# MICRO.net
KiCad netlist of a schematic drawn in Altium Designer
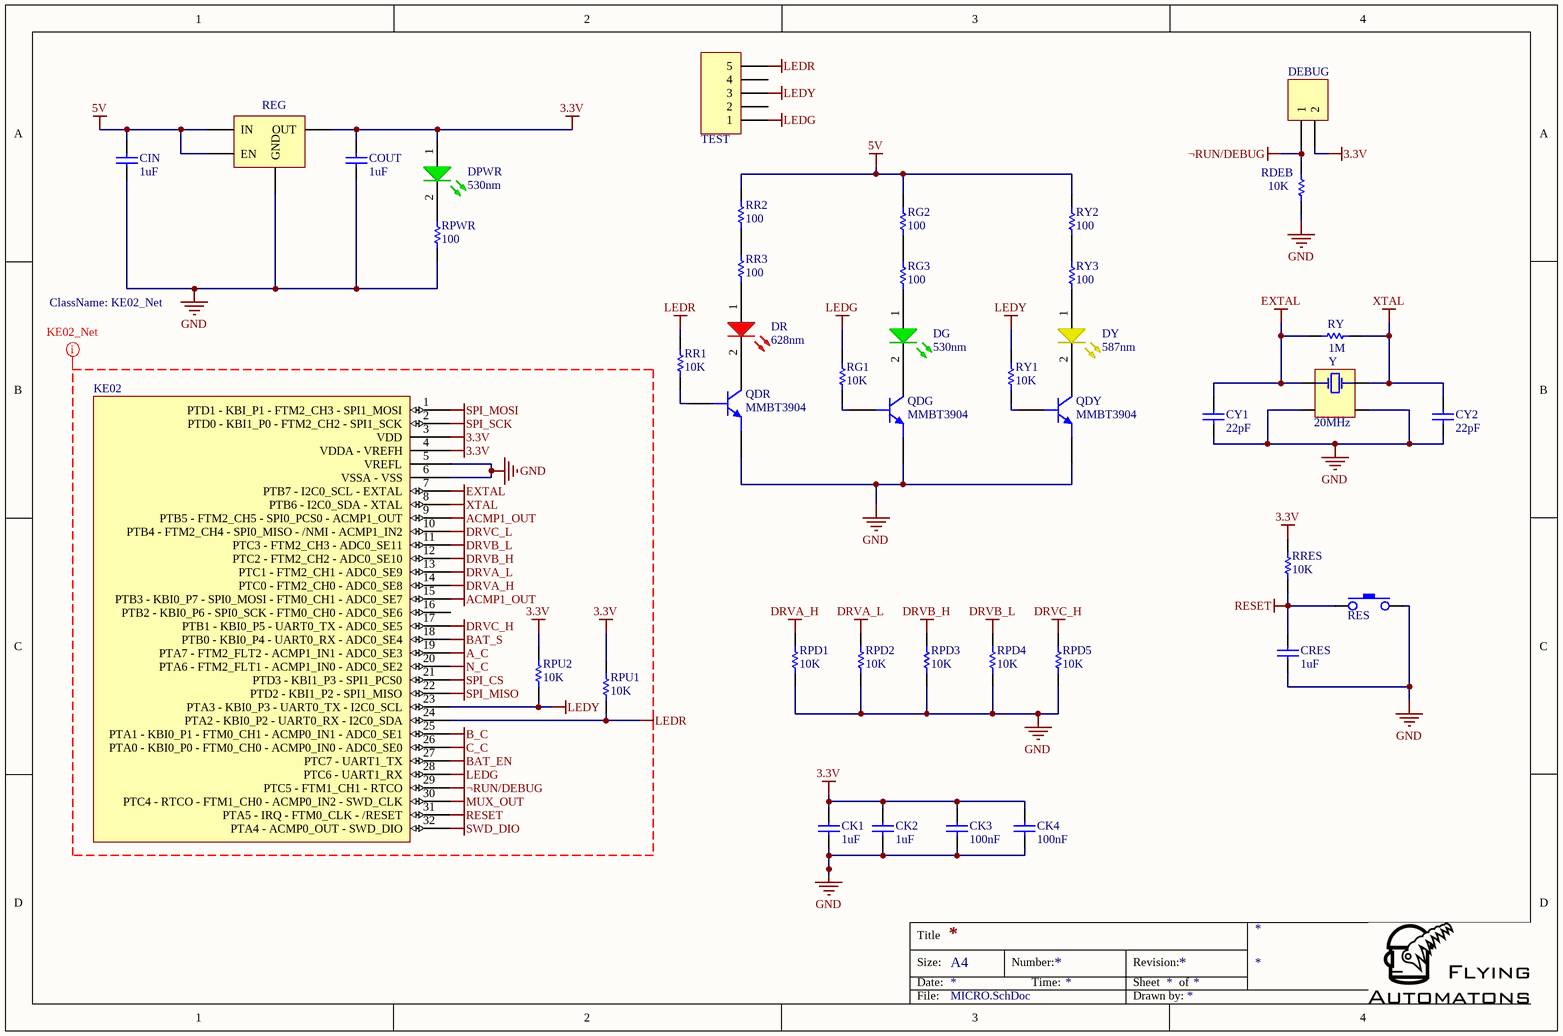
[diagram p0: MICRO.SchDoc]

(export (version "E")
  (design (tool "Eeschema 10.0.6"))
  (components
    (comp (ref "CIN")
      (value "1uF")
      (footprint "CAPC1608L")
      (description "CAP CER 1UF 25V 10% X5R 0603")
      (fields (field (name "MANUFACTURER PART NUMBER") "TMK107BJ105KA-T"))
      (libsource (lib "Passive#csv") (part "CAP_1u_0603_25V_X5R_10%"))
    )
    (comp (ref "CK1")
      (value "1uF")
      (footprint "CAPC1608L")
      (description "CAP CER 1UF 25V 10% X5R 0603")
      (fields (field (name "MANUFACTURER PART NUMBER") "TMK107BJ105KA-T"))
      (libsource (lib "Passive#csv") (part "CAP_1u_0603_25V_X5R_10%"))
    )
    (comp (ref "CK2")
      (value "1uF")
      (footprint "CAPC1608L")
      (description "CAP CER 1UF 25V 10% X5R 0603")
      (fields (field (name "MANUFACTURER PART NUMBER") "TMK107BJ105KA-T"))
      (libsource (lib "Passive#csv") (part "CAP_1u_0603_25V_X5R_10%"))
    )
    (comp (ref "CK3")
      (value "100nF")
      (footprint "CAPC1608L")
      (description "CAP CER 0.1UF 50V Y5V 0603")
      (fields (field (name "MANUFACTURER PART NUMBER") "CC0603ZRY5V9BB104"))
      (libsource (lib "Passive#csv") (part "CAP_100n_0603_50V_Y5V"))
    )
    (comp (ref "CK4")
      (value "100nF")
      (footprint "CAPC1608L")
      (description "CAP CER 0.1UF 50V Y5V 0603")
      (fields (field (name "MANUFACTURER PART NUMBER") "CC0603ZRY5V9BB104"))
      (libsource (lib "Passive#csv") (part "CAP_100n_0603_50V_Y5V"))
    )
    (comp (ref "COUT")
      (value "1uF")
      (footprint "CAPC1608L")
      (description "CAP CER 1UF 25V 10% X5R 0603")
      (fields (field (name "MANUFACTURER PART NUMBER") "TMK107BJ105KA-T"))
      (libsource (lib "Passive#csv") (part "CAP_1u_0603_25V_X5R_10%"))
    )
    (comp (ref "CRES")
      (value "1uF")
      (footprint "CAPC1608L")
      (description "CAP CER 1UF 25V 10% X5R 0603")
      (fields (field (name "MANUFACTURER PART NUMBER") "TMK107BJ105KA-T"))
      (libsource (lib "Passive#csv") (part "CAP_1u_0603_25V_X5R_10%"))
    )
    (comp (ref "CY1")
      (value "22pF")
      (footprint "CAPC1608L")
      (description "CAP CER 22PF 50V 5% NP0 0603")
      (fields (field (name "MANUFACTURER PART NUMBER") "CL10C220JB8NCNC"))
      (libsource (lib "Passive#csv") (part "CAP_22p_0603_50V_NP0_5%"))
    )
    (comp (ref "CY2")
      (value "22pF")
      (footprint "CAPC1608L")
      (description "CAP CER 22PF 50V 5% NP0 0603")
      (fields (field (name "MANUFACTURER PART NUMBER") "CL10C220JB8NCNC"))
      (libsource (lib "Passive#csv") (part "CAP_22p_0603_50V_NP0_5%"))
    )
    (comp (ref "DEBUG")
      (value "Header 2")
      (footprint "Pines 1x2")
      (description "Header, 2-Pin")
      (fields (field (name "PUBLISHER") "Altium Limited"))
      (libsource (lib "ConnectorsGordo") (part "Header 2"))
    )
    (comp (ref "DG")
      (value "530nm")
      (footprint "DSO-F2/D3.4")
      (description "LED CHIPLED 570NM GREEN 0603 SMD")
      (fields
        (field (name "MANUFACTURER") "OSRAM Opto Semiconductors Inc")
        (field (name "MANUFACTURER PART NUMBER") "LG Q971-KN-1")
        (field (name "DRAWN BY") "Juan I Carrano")
      )
      (libsource (lib "Discrete#csv") (part "LED_GREEN_0603_530"))
    )
    (comp (ref "DPWR")
      (value "530nm")
      (footprint "DSO-F2/D3.4")
      (description "LED CHIPLED 570NM GREEN 0603 SMD")
      (fields
        (field (name "MANUFACTURER") "OSRAM Opto Semiconductors Inc")
        (field (name "MANUFACTURER PART NUMBER") "LG Q971-KN-1")
        (field (name "DRAWN BY") "Juan I Carrano")
      )
      (libsource (lib "Discrete#csv") (part "LED_GREEN_0603_530"))
    )
    (comp (ref "DR")
      (value "628nm")
      (footprint "DSO-F2/D3.4")
      (description "LED POINTLED 628NM SUPER RED SMD")
      (fields
        (field (name "MANUFACTURER") "OSRAM Opto Semiconductors Inc")
        (field (name "MANUFACTURER PART NUMBER") "LS Q971-KN-1")
        (field (name "DRAWN BY") "Juan I Carrano")
      )
      (libsource (lib "Discrete#csv") (part "LED_RED_0603_628"))
    )
    (comp (ref "DY")
      (value "587nm")
      (footprint "DSO-F2/D3.4")
      (description "LED CHIPLED 587NM YLW 0603 SMD")
      (fields
        (field (name "MANUFACTURER") "OSRAM Opto Semiconductors Inc")
        (field (name "MANUFACTURER PART NUMBER") "LY Q976-P1S2-36")
        (field (name "DRAWN BY") "Juan I Carrano")
      )
      (libsource (lib "Discrete#csv") (part "LED_YELLOW_0603_587"))
    )
    (comp (ref "KE02")
      (value "MKE02ZxxVLC2(R)")
      (footprint "JEDEC_MS-026BBA")
      (description "Kinetis KE02 Cortex®-M0+ MCU 32 Pin LQFP")
      (fields
        (field (name "MANUFACTURER") "Freescale")
        (field (name "MANUFACTURER PART NUMBER") "MKE02Z64VLC2(R)")
      )
      (libsource (lib "MCU#csv") (part "MKE02Z64VLC2(R)"))
    )
    (comp (ref "QDG")
      (value "MMBT3904")
      (footprint "SOT23-3L")
      (description "TRANSISTOR NPN 40V 0.2A SOT23")
      (fields (field (name "MANUFACTURER") "NXP Semiconductors") (field (name "Comment") "BJT-NPN-BEC"))
      (libsource (lib "Discrete#csv") (part "MMBT3904"))
    )
    (comp (ref "QDR")
      (value "MMBT3904")
      (footprint "SOT23-3L")
      (description "TRANSISTOR NPN 40V 0.2A SOT23")
      (fields (field (name "MANUFACTURER") "NXP Semiconductors") (field (name "Comment") "BJT-NPN-BEC"))
      (libsource (lib "Discrete#csv") (part "MMBT3904"))
    )
    (comp (ref "QDY")
      (value "MMBT3904")
      (footprint "SOT23-3L")
      (description "TRANSISTOR NPN 40V 0.2A SOT23")
      (fields (field (name "MANUFACTURER") "NXP Semiconductors") (field (name "Comment") "BJT-NPN-BEC"))
      (libsource (lib "Discrete#csv") (part "MMBT3904"))
    )
    (comp (ref "RDEB")
      (value "10K")
      (footprint "RESC1608L")
      (description "RES 10K OHM 1/10W 5% 0603")
      (fields (field (name "MANUFACTURER PART NUMBER") "RC1608J103CS"))
      (libsource (lib "Passive#csv") (part "RES_10K_0603_0W1_1%"))
    )
    (comp (ref "REG")
      (value "LP5900")
      (footprint "x-TI_S-NGF0006A")
      (description "IC REG LDO 3.3V 0.15A 6WSON")
      (fields
        (field (name "MANUFACTURER") "Texas Instruments")
        (field (name "MANUFACTURER PART NUMBER") "LP5900SD-3.3/NOPB")
      )
      (libsource (lib "Power_IC#csv") (part "x-TI_LP5900"))
    )
    (comp (ref "RES")
      (value "SWITCH_TACTILE_SPST-2T-NO")
      (footprint "X-TECO_FSMSM")
      (description "SWITCH TACTILE SPST-NO 0.05A 12V")
      (fields
        (field (name "MANUFACTURER") "TE Connectivity")
        (field (name "MANUFACTURER PART NUMBER") "FSMSM")
      )
      (libsource (lib "Switch#csv") (part "SW_TACT_3.5x6mm_SMT"))
    )
    (comp (ref "RG1")
      (value "10K")
      (footprint "RESC1608L")
      (description "RES 10K OHM 1/10W 5% 0603")
      (fields (field (name "MANUFACTURER PART NUMBER") "RC1608J103CS"))
      (libsource (lib "Passive#csv") (part "RES_10K_0603_0W1_1%"))
    )
    (comp (ref "RG2")
      (value "100")
      (footprint "RESC1608L")
      (description "RES 100 OHM 1/10W 5% 0603 SMD")
      (fields (field (name "MANUFACTURER PART NUMBER") "RC0603JR-07100RL"))
      (libsource (lib "Passive#csv") (part "RES_100_0603_0W1_1%"))
    )
    (comp (ref "RG3")
      (value "100")
      (footprint "RESC1608L")
      (description "RES 100 OHM 1/10W 5% 0603 SMD")
      (fields (field (name "MANUFACTURER PART NUMBER") "RC0603JR-07100RL"))
      (libsource (lib "Passive#csv") (part "RES_100_0603_0W1_1%"))
    )
    (comp (ref "RPD1")
      (value "10K")
      (footprint "RESC1608L")
      (description "RES 10K OHM 1/10W 5% 0603")
      (fields (field (name "MANUFACTURER PART NUMBER") "RC1608J103CS"))
      (libsource (lib "Passive#csv") (part "RES_10K_0603_0W1_1%"))
    )
    (comp (ref "RPD2")
      (value "10K")
      (footprint "RESC1608L")
      (description "RES 10K OHM 1/10W 5% 0603")
      (fields (field (name "MANUFACTURER PART NUMBER") "RC1608J103CS"))
      (libsource (lib "Passive#csv") (part "RES_10K_0603_0W1_1%"))
    )
    (comp (ref "RPD3")
      (value "10K")
      (footprint "RESC1608L")
      (description "RES 10K OHM 1/10W 5% 0603")
      (fields (field (name "MANUFACTURER PART NUMBER") "RC1608J103CS"))
      (libsource (lib "Passive#csv") (part "RES_10K_0603_0W1_1%"))
    )
    (comp (ref "RPD4")
      (value "10K")
      (footprint "RESC1608L")
      (description "RES 10K OHM 1/10W 5% 0603")
      (fields (field (name "MANUFACTURER PART NUMBER") "RC1608J103CS"))
      (libsource (lib "Passive#csv") (part "RES_10K_0603_0W1_1%"))
    )
    (comp (ref "RPD5")
      (value "10K")
      (footprint "RESC1608L")
      (description "RES 10K OHM 1/10W 5% 0603")
      (fields (field (name "MANUFACTURER PART NUMBER") "RC1608J103CS"))
      (libsource (lib "Passive#csv") (part "RES_10K_0603_0W1_1%"))
    )
    (comp (ref "RPU1")
      (value "10K")
      (footprint "RESC1608L")
      (description "RES 10K OHM 1/10W 5% 0603")
      (fields (field (name "MANUFACTURER PART NUMBER") "RC1608J103CS"))
      (libsource (lib "Passive#csv") (part "RES_10K_0603_0W1_1%"))
    )
    (comp (ref "RPU2")
      (value "10K")
      (footprint "RESC1608L")
      (description "RES 10K OHM 1/10W 5% 0603")
      (fields (field (name "MANUFACTURER PART NUMBER") "RC1608J103CS"))
      (libsource (lib "Passive#csv") (part "RES_10K_0603_0W1_1%"))
    )
    (comp (ref "RPWR")
      (value "100")
      (footprint "RESC1608L")
      (description "RES 100 OHM 1/10W 5% 0603 SMD")
      (fields (field (name "MANUFACTURER PART NUMBER") "RC0603JR-07100RL"))
      (libsource (lib "Passive#csv") (part "RES_100_0603_0W1_1%"))
    )
    (comp (ref "RR1")
      (value "10K")
      (footprint "RESC1608L")
      (description "RES 10K OHM 1/10W 5% 0603")
      (fields (field (name "MANUFACTURER PART NUMBER") "RC1608J103CS"))
      (libsource (lib "Passive#csv") (part "RES_10K_0603_0W1_1%"))
    )
    (comp (ref "RR2")
      (value "100")
      (footprint "RESC1608L")
      (description "RES 100 OHM 1/10W 5% 0603 SMD")
      (fields (field (name "MANUFACTURER PART NUMBER") "RC0603JR-07100RL"))
      (libsource (lib "Passive#csv") (part "RES_100_0603_0W1_1%"))
    )
    (comp (ref "RR3")
      (value "100")
      (footprint "RESC1608L")
      (description "RES 100 OHM 1/10W 5% 0603 SMD")
      (fields (field (name "MANUFACTURER PART NUMBER") "RC0603JR-07100RL"))
      (libsource (lib "Passive#csv") (part "RES_100_0603_0W1_1%"))
    )
    (comp (ref "RRES")
      (value "10K")
      (footprint "RESC1608L")
      (description "RES 10K OHM 1/10W 5% 0603")
      (fields (field (name "MANUFACTURER PART NUMBER") "RC1608J103CS"))
      (libsource (lib "Passive#csv") (part "RES_10K_0603_0W1_1%"))
    )
    (comp (ref "RY")
      (value "1M")
      (footprint "RESC1608L")
      (description "RES 1.00M OHM 1/10W 1% 0603 SMD")
      (fields
        (field (name "MANUFACTURER") "Yageo")
        (field (name "MANUFACTURER PART NUMBER") "RC0603FR-071ML")
      )
      (libsource (lib "Passive#csv") (part "RES_1M_0603_0W1_1%"))
    )
    (comp (ref "RY1")
      (value "10K")
      (footprint "RESC1608L")
      (description "RES 10K OHM 1/10W 5% 0603")
      (fields (field (name "MANUFACTURER PART NUMBER") "RC1608J103CS"))
      (libsource (lib "Passive#csv") (part "RES_10K_0603_0W1_1%"))
    )
    (comp (ref "RY2")
      (value "100")
      (footprint "RESC1608L")
      (description "RES 100 OHM 1/10W 5% 0603 SMD")
      (fields (field (name "MANUFACTURER PART NUMBER") "RC0603JR-07100RL"))
      (libsource (lib "Passive#csv") (part "RES_100_0603_0W1_1%"))
    )
    (comp (ref "RY3")
      (value "100")
      (footprint "RESC1608L")
      (description "RES 100 OHM 1/10W 5% 0603 SMD")
      (fields (field (name "MANUFACTURER PART NUMBER") "RC0603JR-07100RL"))
      (libsource (lib "Passive#csv") (part "RES_100_0603_0W1_1%"))
    )
    (comp (ref "TEST")
      (value "Header 5")
      (footprint "Pines 1x5")
      (description "Header, 5-Pin")
      (fields (field (name "PUBLISHER") "Altium Limited"))
      (libsource (lib "ConnectorsGordo") (part "Header 5"))
    )
    (comp (ref "Y")
      (value "20MHz")
      (footprint "X-EPSO_TSX-3225")
      (description "CRYSTAL 20MHZ 9PF SMD")
      (fields
        (field (name "MANUFACTURER") "EPSON")
        (field (name "MANUFACTURER PART NUMBER") "TSX-3225 20.0000MF20G-AC3")
        (field (name "DRAWN BY") "Juan I Carrano")
      )
      (libsource (lib "Passive#csv") (part "XTAL_20M_SMD_9p"))
    )
  )
  (nets
    (net (code "1") (name "3.3V") (class "Default")
      (node (ref "CK1") (pin "1") (pinfunction "1_1") (pintype "passive"))
      (node (ref "CK2") (pin "1") (pinfunction "1_1") (pintype "passive"))
      (node (ref "CK3") (pin "1") (pinfunction "1_1") (pintype "passive"))
      (node (ref "CK4") (pin "1") (pinfunction "1_1") (pintype "passive"))
      (node (ref "COUT") (pin "1") (pinfunction "1_1") (pintype "passive"))
      (node (ref "DEBUG") (pin "2") (pinfunction "2_2") (pintype "passive"))
      (node (ref "DPWR") (pin "1") (pinfunction "A_1") (pintype "passive"))
      (node (ref "KE02") (pin "3") (pinfunction "VDD_3") (pintype "passive"))
      (node (ref "KE02") (pin "4") (pinfunction "VDDA_-_VREFH_4") (pintype "passive"))
      (node (ref "REG") (pin "1") (pinfunction "OUT_1") (pintype "passive"))
      (node (ref "RPU1") (pin "1") (pinfunction "1_1") (pintype "passive"))
      (node (ref "RPU2") (pin "1") (pinfunction "1_1") (pintype "passive"))
      (node (ref "RRES") (pin "1") (pinfunction "1_1") (pintype "passive"))
    )
    (net (code "2") (name "5V") (class "Default")
      (node (ref "CIN") (pin "1") (pinfunction "1_1") (pintype "passive"))
      (node (ref "REG") (pin "4") (pinfunction "EN_4") (pintype "passive"))
      (node (ref "REG") (pin "6") (pinfunction "IN_6") (pintype "passive"))
      (node (ref "RG2") (pin "1") (pinfunction "1_1") (pintype "passive"))
      (node (ref "RR2") (pin "1") (pinfunction "1_1") (pintype "passive"))
      (node (ref "RY2") (pin "1") (pinfunction "1_1") (pintype "passive"))
    )
    (net (code "3") (name "ACMP1_OUT") (class "Default")
      (node (ref "KE02") (pin "15") (pinfunction "PTB3_-_KBI0_P7_-_SPI0_MOSI_-_FTM0_CH1_-_ADC0_SE7_15") (pintype "bidirectional"))
      (node (ref "KE02") (pin "9") (pinfunction "PTB5_-_FTM2_CH5_-_SPI0_PCS0_-_ACMP1_OUT_9") (pintype "bidirectional"))
    )
    (net (code "4") (name "A_C") (class "Default")
      (node (ref "KE02") (pin "19") (pinfunction "PTA7_-_FTM2_FLT2_-_ACMP1_IN1_-_ADC0_SE3_19") (pintype "bidirectional"))
    )
    (net (code "5") (name "BAT_EN") (class "Default")
      (node (ref "KE02") (pin "27") (pinfunction "PTC7_-_UART1_TX_27") (pintype "bidirectional"))
    )
    (net (code "6") (name "BAT_S") (class "Default")
      (node (ref "KE02") (pin "18") (pinfunction "PTB0_-_KBI0_P4_-_UART0_RX_-_ADC0_SE4_18") (pintype "bidirectional"))
    )
    (net (code "7") (name "B_C") (class "Default")
      (node (ref "KE02") (pin "25") (pinfunction "PTA1_-_KBI0_P1_-_FTM0_CH1_-_ACMP0_IN1_-_ADC0_SE1_25") (pintype "bidirectional"))
    )
    (net (code "8") (name "C_C") (class "Default")
      (node (ref "KE02") (pin "26") (pinfunction "PTA0_-_KBI0_P0_-_FTM0_CH0_-_ACMP0_IN0_-_ADC0_SE0_26") (pintype "bidirectional"))
    )
    (net (code "9") (name "DRVA_H") (class "Default")
      (node (ref "KE02") (pin "14") (pinfunction "PTC0_-_FTM2_CH0_-_ADC0_SE8_14") (pintype "bidirectional"))
      (node (ref "RPD1") (pin "1") (pinfunction "1_1") (pintype "passive"))
    )
    (net (code "10") (name "DRVA_L") (class "Default")
      (node (ref "KE02") (pin "13") (pinfunction "PTC1_-_FTM2_CH1_-_ADC0_SE9_13") (pintype "bidirectional"))
      (node (ref "RPD2") (pin "1") (pinfunction "1_1") (pintype "passive"))
    )
    (net (code "11") (name "DRVB_H") (class "Default")
      (node (ref "KE02") (pin "12") (pinfunction "PTC2_-_FTM2_CH2_-_ADC0_SE10_12") (pintype "bidirectional"))
      (node (ref "RPD3") (pin "1") (pinfunction "1_1") (pintype "passive"))
    )
    (net (code "12") (name "DRVB_L") (class "Default")
      (node (ref "KE02") (pin "11") (pinfunction "PTC3_-_FTM2_CH3_-_ADC0_SE11_11") (pintype "bidirectional"))
      (node (ref "RPD4") (pin "1") (pinfunction "1_1") (pintype "passive"))
    )
    (net (code "13") (name "DRVC_H") (class "Default")
      (node (ref "KE02") (pin "17") (pinfunction "PTB1_-_KBI0_P5_-_UART0_TX_-_ADC0_SE5_17") (pintype "bidirectional"))
      (node (ref "RPD5") (pin "1") (pinfunction "1_1") (pintype "passive"))
    )
    (net (code "14") (name "DRVC_L") (class "Default")
      (node (ref "KE02") (pin "10") (pinfunction "PTB4_-_FTM2_CH4_-_SPI0_MISO_-_/NMI_-_ACMP1_IN2_10") (pintype "bidirectional"))
    )
    (net (code "15") (name "EXTAL") (class "Default")
      (node (ref "CY1") (pin "1") (pinfunction "1_1") (pintype "passive"))
      (node (ref "KE02") (pin "7") (pinfunction "PTB7_-_I2C0_SCL_-_EXTAL_7") (pintype "bidirectional"))
      (node (ref "RY") (pin "2") (pinfunction "2_2") (pintype "passive"))
      (node (ref "Y") (pin "1") (pinfunction "1_1") (pintype "passive"))
    )
    (net (code "16") (name "GND") (class "Default")
      (node (ref "CIN") (pin "2") (pinfunction "2_2") (pintype "passive"))
      (node (ref "CK1") (pin "2") (pinfunction "2_2") (pintype "passive"))
      (node (ref "CK2") (pin "2") (pinfunction "2_2") (pintype "passive"))
      (node (ref "CK3") (pin "2") (pinfunction "2_2") (pintype "passive"))
      (node (ref "CK4") (pin "2") (pinfunction "2_2") (pintype "passive"))
      (node (ref "COUT") (pin "2") (pinfunction "2_2") (pintype "passive"))
      (node (ref "CRES") (pin "1") (pinfunction "1_1") (pintype "passive"))
      (node (ref "CY1") (pin "2") (pinfunction "2_2") (pintype "passive"))
      (node (ref "CY2") (pin "2") (pinfunction "2_2") (pintype "passive"))
      (node (ref "KE02") (pin "5") (pinfunction "VREFL_5") (pintype "passive"))
      (node (ref "KE02") (pin "6") (pinfunction "VSSA_-_VSS_6") (pintype "passive"))
      (node (ref "QDG") (pin "2") (pinfunction "E_2") (pintype "passive"))
      (node (ref "QDR") (pin "2") (pinfunction "E_2") (pintype "passive"))
      (node (ref "QDY") (pin "2") (pinfunction "E_2") (pintype "passive"))
      (node (ref "RDEB") (pin "2") (pinfunction "2_2") (pintype "passive"))
      (node (ref "REG") (pin "3") (pinfunction "GND_3") (pintype "passive"))
      (node (ref "RES") (pin "2") (pinfunction "2_2") (pintype "passive"))
      (node (ref "RPD1") (pin "2") (pinfunction "2_2") (pintype "passive"))
      (node (ref "RPD2") (pin "2") (pinfunction "2_2") (pintype "passive"))
      (node (ref "RPD3") (pin "2") (pinfunction "2_2") (pintype "passive"))
      (node (ref "RPD4") (pin "2") (pinfunction "2_2") (pintype "passive"))
      (node (ref "RPD5") (pin "2") (pinfunction "2_2") (pintype "passive"))
      (node (ref "RPWR") (pin "2") (pinfunction "2_2") (pintype "passive"))
      (node (ref "Y") (pin "2") (pinfunction "2_2") (pintype "passive"))
      (node (ref "Y") (pin "4") (pinfunction "4_4") (pintype "passive"))
    )
    (net (code "17") (name "LEDG") (class "Default")
      (node (ref "KE02") (pin "28") (pinfunction "PTC6_-_UART1_RX_28") (pintype "bidirectional"))
      (node (ref "RG1") (pin "1") (pinfunction "1_1") (pintype "passive"))
      (node (ref "TEST") (pin "1") (pinfunction "1_1") (pintype "passive"))
    )
    (net (code "18") (name "LEDR") (class "Default")
      (node (ref "KE02") (pin "24") (pinfunction "PTA2_-_KBI0_P2_-_UART0_RX_-_I2C0_SDA_24") (pintype "bidirectional"))
      (node (ref "RPU1") (pin "2") (pinfunction "2_2") (pintype "passive"))
      (node (ref "RR1") (pin "1") (pinfunction "1_1") (pintype "passive"))
      (node (ref "TEST") (pin "5") (pinfunction "5_5") (pintype "passive"))
    )
    (net (code "19") (name "LEDY") (class "Default")
      (node (ref "KE02") (pin "23") (pinfunction "PTA3_-_KBI0_P3_-_UART0_TX_-_I2C0_SCL_23") (pintype "bidirectional"))
      (node (ref "RPU2") (pin "2") (pinfunction "2_2") (pintype "passive"))
      (node (ref "RY1") (pin "1") (pinfunction "1_1") (pintype "passive"))
      (node (ref "TEST") (pin "3") (pinfunction "3_3") (pintype "passive"))
    )
    (net (code "20") (name "MUX_OUT") (class "Default")
      (node (ref "KE02") (pin "30") (pinfunction "PTC4_-_RTCO_-_FTM1_CH0_-_ACMP0_IN2_-_SWD_CLK_30") (pintype "bidirectional"))
    )
    (net (code "21") (name "N_C") (class "Default")
      (node (ref "KE02") (pin "20") (pinfunction "PTA6_-_FTM2_FLT1_-_ACMP1_IN0_-_ADC0_SE2_20") (pintype "bidirectional"))
    )
    (net (code "22") (name "Net-(DG-A)") (class "Default")
      (node (ref "DG") (pin "1") (pinfunction "A_1") (pintype "passive"))
      (node (ref "RG3") (pin "2") (pinfunction "2_2") (pintype "passive"))
    )
    (net (code "23") (name "Net-(DG-K)") (class "Default")
      (node (ref "DG") (pin "2") (pinfunction "K_2") (pintype "passive"))
      (node (ref "QDG") (pin "3") (pinfunction "C_3") (pintype "passive"))
    )
    (net (code "24") (name "Net-(DPWR-K)") (class "Default")
      (node (ref "DPWR") (pin "2") (pinfunction "K_2") (pintype "passive"))
      (node (ref "RPWR") (pin "1") (pinfunction "1_1") (pintype "passive"))
    )
    (net (code "25") (name "Net-(DR-A)") (class "Default")
      (node (ref "DR") (pin "1") (pinfunction "A_1") (pintype "passive"))
      (node (ref "RR3") (pin "2") (pinfunction "2_2") (pintype "passive"))
    )
    (net (code "26") (name "Net-(DR-K)") (class "Default")
      (node (ref "DR") (pin "2") (pinfunction "K_2") (pintype "passive"))
      (node (ref "QDR") (pin "3") (pinfunction "C_3") (pintype "passive"))
    )
    (net (code "27") (name "Net-(DY-A)") (class "Default")
      (node (ref "DY") (pin "1") (pinfunction "A_1") (pintype "passive"))
      (node (ref "RY3") (pin "2") (pinfunction "2_2") (pintype "passive"))
    )
    (net (code "28") (name "Net-(DY-K)") (class "Default")
      (node (ref "DY") (pin "2") (pinfunction "K_2") (pintype "passive"))
      (node (ref "QDY") (pin "3") (pinfunction "C_3") (pintype "passive"))
    )
    (net (code "29") (name "Net-(QDG-B)") (class "Default")
      (node (ref "QDG") (pin "1") (pinfunction "B_1") (pintype "passive"))
      (node (ref "RG1") (pin "2") (pinfunction "2_2") (pintype "passive"))
    )
    (net (code "30") (name "Net-(QDR-B)") (class "Default")
      (node (ref "QDR") (pin "1") (pinfunction "B_1") (pintype "passive"))
      (node (ref "RR1") (pin "2") (pinfunction "2_2") (pintype "passive"))
    )
    (net (code "31") (name "Net-(QDY-B)") (class "Default")
      (node (ref "QDY") (pin "1") (pinfunction "B_1") (pintype "passive"))
      (node (ref "RY1") (pin "2") (pinfunction "2_2") (pintype "passive"))
    )
    (net (code "32") (name "Net-(RG2-Pad2)") (class "Default")
      (node (ref "RG2") (pin "2") (pinfunction "2_2") (pintype "passive"))
      (node (ref "RG3") (pin "1") (pinfunction "1_1") (pintype "passive"))
    )
    (net (code "33") (name "Net-(RR2-Pad2)") (class "Default")
      (node (ref "RR2") (pin "2") (pinfunction "2_2") (pintype "passive"))
      (node (ref "RR3") (pin "1") (pinfunction "1_1") (pintype "passive"))
    )
    (net (code "34") (name "Net-(RY2-Pad2)") (class "Default")
      (node (ref "RY2") (pin "2") (pinfunction "2_2") (pintype "passive"))
      (node (ref "RY3") (pin "1") (pinfunction "1_1") (pintype "passive"))
    )
    (net (code "35") (name "RESET") (class "Default")
      (node (ref "CRES") (pin "2") (pinfunction "2_2") (pintype "passive"))
      (node (ref "KE02") (pin "31") (pinfunction "PTA5_-_IRQ_-_FTM0_CLK_-_/RESET_31") (pintype "bidirectional"))
      (node (ref "RES") (pin "1") (pinfunction "1_1") (pintype "passive"))
      (node (ref "RRES") (pin "2") (pinfunction "2_2") (pintype "passive"))
    )
    (net (code "36") (name "SPI_CS") (class "Default")
      (node (ref "KE02") (pin "21") (pinfunction "PTD3_-_KBI1_P3_-_SPI1_PCS0_21") (pintype "bidirectional"))
    )
    (net (code "37") (name "SPI_MISO") (class "Default")
      (node (ref "KE02") (pin "22") (pinfunction "PTD2_-_KBI1_P2_-_SPI1_MISO_22") (pintype "bidirectional"))
    )
    (net (code "38") (name "SPI_MOSI") (class "Default")
      (node (ref "KE02") (pin "1") (pinfunction "PTD1_-_KBI_P1_-_FTM2_CH3_-_SPI1_MOSI_1") (pintype "bidirectional"))
    )
    (net (code "39") (name "SPI_SCK") (class "Default")
      (node (ref "KE02") (pin "2") (pinfunction "PTD0_-_KBI1_P0_-_FTM2_CH2_-_SPI1_SCK_2") (pintype "bidirectional"))
    )
    (net (code "40") (name "SWD_DIO") (class "Default")
      (node (ref "KE02") (pin "32") (pinfunction "PTA4_-_ACMP0_OUT_-_SWD_DIO_32") (pintype "bidirectional"))
    )
    (net (code "41") (name "XTAL") (class "Default")
      (node (ref "CY2") (pin "1") (pinfunction "1_1") (pintype "passive"))
      (node (ref "KE02") (pin "8") (pinfunction "PTB6_-_I2C0_SDA_-_XTAL_8") (pintype "bidirectional"))
      (node (ref "RY") (pin "1") (pinfunction "1_1") (pintype "passive"))
      (node (ref "Y") (pin "3") (pinfunction "3_3") (pintype "passive"))
    )
    (net (code "42") (name "unconnected-(KE02-PTB2_-_KBI0_P6_-_SPI0_SCK_-_FTM0_CH0_-_ADC0_SE6-Pad16)") (class "Default")
      (node (ref "KE02") (pin "16") (pinfunction "PTB2_-_KBI0_P6_-_SPI0_SCK_-_FTM0_CH0_-_ADC0_SE6_16") (pintype "bidirectional"))
    )
    (net (code "43") (name "unconnected-(TEST-Pad2)") (class "Default")
      (node (ref "TEST") (pin "2") (pinfunction "2_2") (pintype "passive"))
    )
    (net (code "44") (name "unconnected-(TEST-Pad4)") (class "Default")
      (node (ref "TEST") (pin "4") (pinfunction "4_4") (pintype "passive"))
    )
    (net (code "45") (name "¬RUN{slash}DEBUG") (class "Default")
      (node (ref "DEBUG") (pin "1") (pinfunction "1_1") (pintype "passive"))
      (node (ref "KE02") (pin "29") (pinfunction "PTC5_-_FTM1_CH1_-_RTCO_29") (pintype "bidirectional"))
      (node (ref "RDEB") (pin "1") (pinfunction "1_1") (pintype "passive"))
    )
  )
)
